# PIC18F25k50-USB_PicKit3-Board.net
KiCad netlist of a schematic drawn in EAGLE
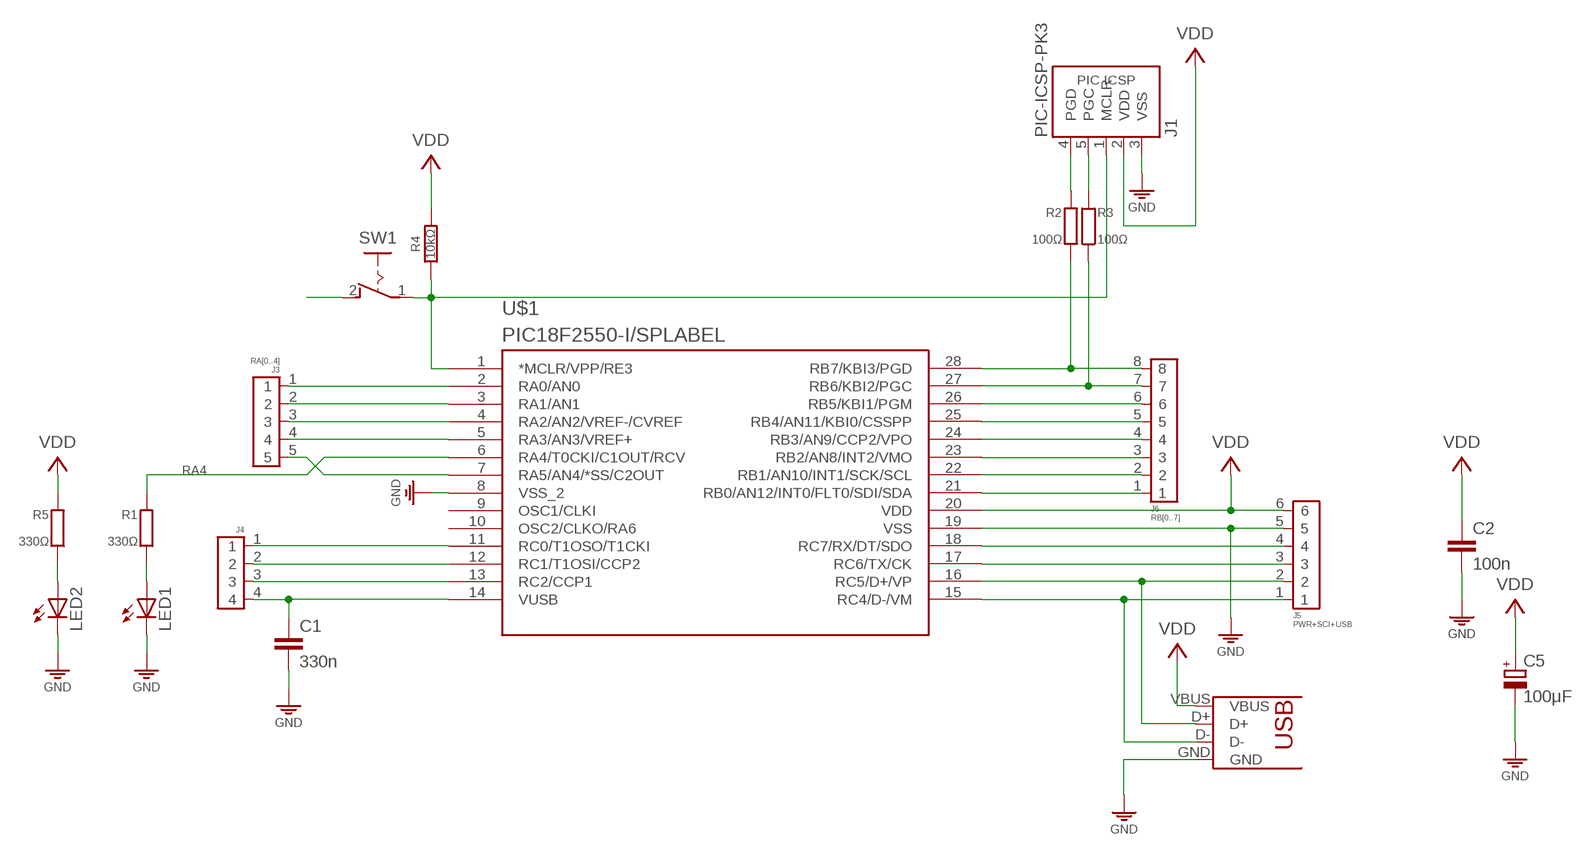
[diagram p0: schematic, sheet 1]

(export (version "E")
  (design (tool "Eeschema 10.0.6"))
  (components
    (comp (ref "C1")
      (value "330n")
      (footprint "eagle-import:C050-030X075")
      (libsource (lib "eagle-import") (part "C050-030X075"))
    )
    (comp (ref "C2")
      (value "100n")
      (footprint "eagle-import:C025-015X024")
      (libsource (lib "eagle-import") (part "C025-015X024"))
    )
    (comp (ref "C5")
      (value "100μF")
      (footprint "eagle-import:E2,5-5")
      (libsource (lib "eagle-import") (part "CPOLE2.5-5"))
    )
    (comp (ref "J1")
      (value "PIC-ICSP-PK3")
      (footprint "eagle-import:PIC-PK3")
      (libsource (lib "eagle-import") (part "PIC-ICSP-PK3"))
    )
    (comp (ref "J2")
      (value "USB-PRINT")
      (footprint "eagle-import:USB-B-PRINT")
      (libsource (lib "eagle-import") (part "USB-PRINT"))
    )
    (comp (ref "J3")
      (value "RA[0..4]")
      (footprint "eagle-import:CONN-5P-N")
      (libsource (lib "eagle-import") (part "CONN-5P"))
    )
    (comp (ref "J4")
      (value "RC[0..3]")
      (footprint "eagle-import:CONN-4P")
      (libsource (lib "eagle-import") (part "CONN-4P-4P"))
    )
    (comp (ref "J5")
      (value "PWR+SCI+USB")
      (footprint "eagle-import:CONN-6P")
      (libsource (lib "eagle-import") (part "CONN-6P"))
    )
    (comp (ref "J6")
      (value "RB[0..7]")
      (footprint "eagle-import:CONN-8P")
      (libsource (lib "eagle-import") (part "CONN-8P"))
    )
    (comp (ref "LED1")
      (value "LED5MM")
      (footprint "eagle-import:LED5MM")
      (libsource (lib "eagle-import") (part "LED5MM"))
    )
    (comp (ref "LED2")
      (value "LED5MM")
      (footprint "eagle-import:LED5MM")
      (libsource (lib "eagle-import") (part "LED5MM"))
    )
    (comp (ref "R1")
      (value "330Ω")
      (footprint "eagle-import:0204_10")
      (libsource (lib "eagle-import") (part "R0204/10"))
    )
    (comp (ref "R2")
      (value "100Ω")
      (footprint "eagle-import:0204_7-V")
      (libsource (lib "eagle-import") (part "R0204/7-V"))
    )
    (comp (ref "R3")
      (value "100Ω")
      (footprint "eagle-import:0204_7-V")
      (libsource (lib "eagle-import") (part "R0204/7-V"))
    )
    (comp (ref "R4")
      (value "10kΩ")
      (footprint "eagle-import:0204_10")
      (libsource (lib "eagle-import") (part "R-H0204/10"))
    )
    (comp (ref "R5")
      (value "330Ω")
      (footprint "eagle-import:0204_10")
      (libsource (lib "eagle-import") (part "R0204/10"))
    )
    (comp (ref "SW1")
      (value "PB-1P-1T")
      (footprint "eagle-import:PB-1P1T")
      (libsource (lib "eagle-import") (part "PB-1P-1T"))
    )
    (comp (ref "U$1")
      (value "PIC18F2550-I/SPLABEL")
      (footprint "eagle-import:PIC18F2550-V")
      (libsource (lib "eagle-import") (part "PIC18F2550-I/SPLABEL"))
    )
  )
  (nets
    (net (code "1") (name "/RA4") (class "Default")
      (node (ref "R1") (pin "1") (pinfunction "2_1") (pintype "passive"))
      (node (ref "U$1") (pin "6") (pinfunction "RA4/T0CKI/C1OUT/RCV_6") (pintype "passive"))
    )
    (net (code "2") (name "GND") (class "Default")
      (node (ref "C1") (pin "2") (pinfunction "2_2") (pintype "passive"))
      (node (ref "C2") (pin "2") (pinfunction "2_2") (pintype "passive"))
      (node (ref "C5") (pin "-") (pinfunction "-_-") (pintype "passive"))
      (node (ref "J1") (pin "3") (pinfunction "VSS_3") (pintype "passive"))
      (node (ref "J2") (pin "GND") (pinfunction "GND_GND") (pintype "bidirectional"))
      (node (ref "J5") (pin "5") (pinfunction "5_5") (pintype "passive"))
      (node (ref "LED1") (pin "K") (pinfunction "C_K") (pintype "passive"))
      (node (ref "LED2") (pin "K") (pinfunction "C_K") (pintype "passive"))
      (node (ref "SW1") (pin "2") (pinfunction "S_2") (pintype "passive"))
      (node (ref "U$1") (pin "19") (pinfunction "VSS_19") (pintype "passive"))
      (node (ref "U$1") (pin "8") (pinfunction "VSS_2_8") (pintype "passive"))
    )
    (net (code "3") (name "Net-(J1-MCLR)") (class "Default")
      (node (ref "J1") (pin "1") (pinfunction "MCLR_1") (pintype "passive"))
      (node (ref "R4") (pin "1") (pinfunction "1_1") (pintype "passive"))
      (node (ref "SW1") (pin "1") (pinfunction "P_1") (pintype "passive"))
      (node (ref "U$1") (pin "1") (pinfunction "*MCLR/VPP/RE3_1") (pintype "passive"))
    )
    (net (code "4") (name "Net-(J1-PGC)") (class "Default")
      (node (ref "J1") (pin "5") (pinfunction "PGC_5") (pintype "passive"))
      (node (ref "R3") (pin "1") (pinfunction "2_1") (pintype "passive"))
    )
    (net (code "5") (name "Net-(J1-PGD)") (class "Default")
      (node (ref "J1") (pin "4") (pinfunction "PGD_4") (pintype "passive"))
      (node (ref "R2") (pin "1") (pinfunction "2_1") (pintype "passive"))
    )
    (net (code "6") (name "Net-(R1-1)") (class "Default")
      (node (ref "LED1") (pin "A") (pinfunction "A_A") (pintype "passive"))
      (node (ref "R1") (pin "2") (pinfunction "1_2") (pintype "passive"))
    )
    (net (code "7") (name "Net-(R2-1)") (class "Default")
      (node (ref "J6") (pin "8") (pinfunction "8_8") (pintype "passive"))
      (node (ref "R2") (pin "2") (pinfunction "1_2") (pintype "passive"))
      (node (ref "U$1") (pin "28") (pinfunction "RB7/KBI3/PGD_28") (pintype "passive"))
    )
    (net (code "8") (name "Net-(R3-1)") (class "Default")
      (node (ref "J6") (pin "7") (pinfunction "7_7") (pintype "passive"))
      (node (ref "R3") (pin "2") (pinfunction "1_2") (pintype "passive"))
      (node (ref "U$1") (pin "27") (pinfunction "RB6/KBI2/PGC_27") (pintype "passive"))
    )
    (net (code "9") (name "Net-(R5-1)") (class "Default")
      (node (ref "LED2") (pin "A") (pinfunction "A_A") (pintype "passive"))
      (node (ref "R5") (pin "2") (pinfunction "1_2") (pintype "passive"))
    )
    (net (code "10") (name "Net-(U$1-RA0{slash}AN0)") (class "Default")
      (node (ref "J3") (pin "1") (pinfunction "1_1") (pintype "passive"))
      (node (ref "U$1") (pin "2") (pinfunction "RA0/AN0_2") (pintype "passive"))
    )
    (net (code "11") (name "Net-(U$1-RA1{slash}AN1)") (class "Default")
      (node (ref "J3") (pin "2") (pinfunction "2_2") (pintype "passive"))
      (node (ref "U$1") (pin "3") (pinfunction "RA1/AN1_3") (pintype "passive"))
    )
    (net (code "12") (name "Net-(U$1-RA2{slash}AN2{slash}VREF-{slash}CVREF)") (class "Default")
      (node (ref "J3") (pin "3") (pinfunction "3_3") (pintype "passive"))
      (node (ref "U$1") (pin "4") (pinfunction "RA2/AN2/VREF-/CVREF_4") (pintype "passive"))
    )
    (net (code "13") (name "Net-(U$1-RA3{slash}AN3{slash}VREF+)") (class "Default")
      (node (ref "J3") (pin "4") (pinfunction "4_4") (pintype "passive"))
      (node (ref "U$1") (pin "5") (pinfunction "RA3/AN3/VREF+_5") (pintype "passive"))
    )
    (net (code "14") (name "Net-(U$1-RA5{slash}AN4{slash}*SS{slash}C2OUT)") (class "Default")
      (node (ref "J3") (pin "5") (pinfunction "5_5") (pintype "passive"))
      (node (ref "U$1") (pin "7") (pinfunction "RA5/AN4/*SS/C2OUT_7") (pintype "passive"))
    )
    (net (code "15") (name "Net-(U$1-RB0{slash}AN12{slash}INT0{slash}FLT0{slash}SDI{slash}SDA)") (class "Default")
      (node (ref "J6") (pin "1") (pinfunction "1_1") (pintype "passive"))
      (node (ref "U$1") (pin "21") (pinfunction "RB0/AN12/INT0/FLT0/SDI/SDA_21") (pintype "passive"))
    )
    (net (code "16") (name "Net-(U$1-RB1{slash}AN10{slash}INT1{slash}SCK{slash}SCL)") (class "Default")
      (node (ref "J6") (pin "2") (pinfunction "2_2") (pintype "passive"))
      (node (ref "U$1") (pin "22") (pinfunction "RB1/AN10/INT1/SCK/SCL_22") (pintype "passive"))
    )
    (net (code "17") (name "Net-(U$1-RB2{slash}AN8{slash}INT2{slash}VMO)") (class "Default")
      (node (ref "J6") (pin "3") (pinfunction "3_3") (pintype "passive"))
      (node (ref "U$1") (pin "23") (pinfunction "RB2/AN8/INT2/VMO_23") (pintype "passive"))
    )
    (net (code "18") (name "Net-(U$1-RB3{slash}AN9{slash}CCP2{slash}VPO)") (class "Default")
      (node (ref "J6") (pin "4") (pinfunction "4_4") (pintype "passive"))
      (node (ref "U$1") (pin "24") (pinfunction "RB3/AN9/CCP2/VPO_24") (pintype "passive"))
    )
    (net (code "19") (name "Net-(U$1-RB4{slash}AN11{slash}KBI0{slash}CSSPP)") (class "Default")
      (node (ref "J6") (pin "5") (pinfunction "5_5") (pintype "passive"))
      (node (ref "U$1") (pin "25") (pinfunction "RB4/AN11/KBI0/CSSPP_25") (pintype "passive"))
    )
    (net (code "20") (name "Net-(U$1-RB5{slash}KBI1{slash}PGM)") (class "Default")
      (node (ref "J6") (pin "6") (pinfunction "6_6") (pintype "passive"))
      (node (ref "U$1") (pin "26") (pinfunction "RB5/KBI1/PGM_26") (pintype "passive"))
    )
    (net (code "21") (name "Net-(U$1-RC0{slash}T1OSO{slash}T1CKI)") (class "Default")
      (node (ref "J4") (pin "1") (pinfunction "1_1") (pintype "bidirectional"))
      (node (ref "U$1") (pin "11") (pinfunction "RC0/T1OSO/T1CKI_11") (pintype "passive"))
    )
    (net (code "22") (name "Net-(U$1-RC1{slash}T1OSI{slash}CCP2)") (class "Default")
      (node (ref "J4") (pin "2") (pinfunction "2_2") (pintype "bidirectional"))
      (node (ref "U$1") (pin "12") (pinfunction "RC1/T1OSI/CCP2_12") (pintype "passive"))
    )
    (net (code "23") (name "Net-(U$1-RC2{slash}CCP1)") (class "Default")
      (node (ref "J4") (pin "3") (pinfunction "3_3") (pintype "bidirectional"))
      (node (ref "U$1") (pin "13") (pinfunction "RC2/CCP1_13") (pintype "passive"))
    )
    (net (code "24") (name "Net-(U$1-RC4{slash}D-{slash}VM)") (class "Default")
      (node (ref "J2") (pin "D-") (pinfunction "D-_D-") (pintype "bidirectional"))
      (node (ref "J5") (pin "1") (pinfunction "1_1") (pintype "passive"))
      (node (ref "U$1") (pin "15") (pinfunction "RC4/D-/VM_15") (pintype "passive"))
    )
    (net (code "25") (name "Net-(U$1-RC5{slash}D+{slash}VP)") (class "Default")
      (node (ref "J2") (pin "D+") (pinfunction "D+_D+") (pintype "bidirectional"))
      (node (ref "J5") (pin "2") (pinfunction "2_2") (pintype "passive"))
      (node (ref "U$1") (pin "16") (pinfunction "RC5/D+/VP_16") (pintype "passive"))
    )
    (net (code "26") (name "Net-(U$1-RC6{slash}TX{slash}CK)") (class "Default")
      (node (ref "J5") (pin "3") (pinfunction "3_3") (pintype "passive"))
      (node (ref "U$1") (pin "17") (pinfunction "RC6/TX/CK_17") (pintype "passive"))
    )
    (net (code "27") (name "Net-(U$1-RC7{slash}RX{slash}DT{slash}SDO)") (class "Default")
      (node (ref "J5") (pin "4") (pinfunction "4_4") (pintype "passive"))
      (node (ref "U$1") (pin "18") (pinfunction "RC7/RX/DT/SDO_18") (pintype "passive"))
    )
    (net (code "28") (name "Net-(U$1-VUSB)") (class "Default")
      (node (ref "C1") (pin "1") (pinfunction "1_1") (pintype "passive"))
      (node (ref "J4") (pin "4") (pinfunction "4_4") (pintype "bidirectional"))
      (node (ref "U$1") (pin "14") (pinfunction "VUSB_14") (pintype "passive"))
    )
    (net (code "29") (name "VDD") (class "Default")
      (node (ref "C2") (pin "1") (pinfunction "1_1") (pintype "passive"))
      (node (ref "C5") (pin "+") (pinfunction "+_+") (pintype "passive"))
      (node (ref "J1") (pin "2") (pinfunction "VDD_2") (pintype "passive"))
      (node (ref "J2") (pin "VBUS") (pinfunction "VBUS_VBUS") (pintype "bidirectional"))
      (node (ref "J5") (pin "6") (pinfunction "6_6") (pintype "passive"))
      (node (ref "R4") (pin "2") (pinfunction "2_2") (pintype "passive"))
      (node (ref "R5") (pin "1") (pinfunction "2_1") (pintype "passive"))
      (node (ref "U$1") (pin "20") (pinfunction "VDD_20") (pintype "passive"))
    )
    (net (code "30") (name "unconnected-(U$1-OSC1{slash}CLKI-Pad9)") (class "Default")
      (node (ref "U$1") (pin "9") (pinfunction "OSC1/CLKI_9") (pintype "passive"))
    )
    (net (code "31") (name "unconnected-(U$1-OSC2{slash}CLKO{slash}RA6-Pad10)") (class "Default")
      (node (ref "U$1") (pin "10") (pinfunction "OSC2/CLKO/RA6_10") (pintype "passive"))
    )
  )
)
